# PinOut_5.net
KiCad netlist of a schematic drawn in EAGLE
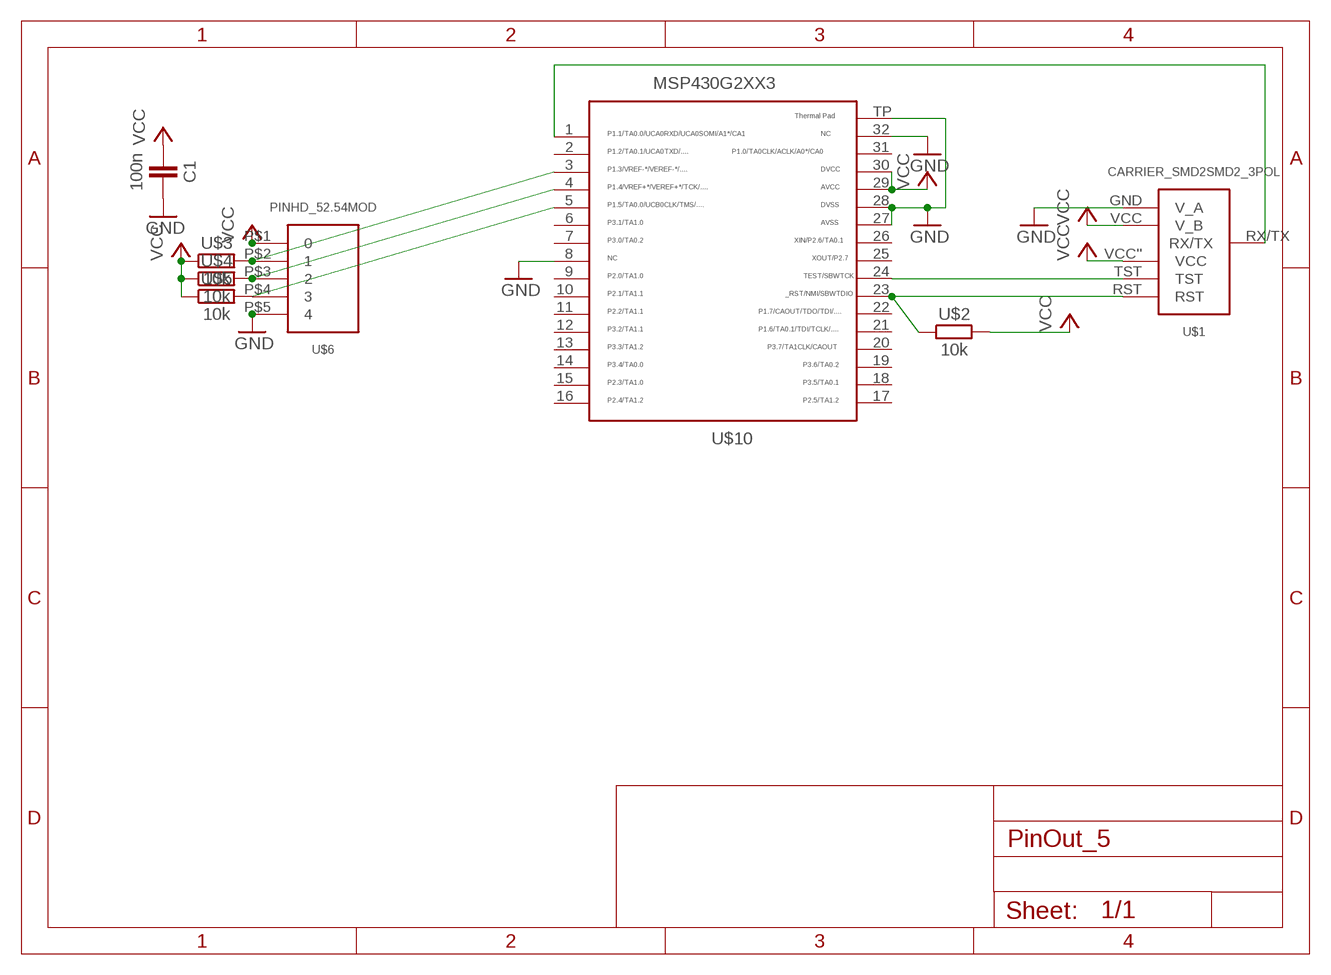
[diagram p0: schematic, sheet 1]

(export (version "E")
  (design (tool "Eeschema 10.0.6"))
  (components
    (comp (ref "C1")
      (value "100n")
      (footprint "eagle-import:603")
      (libsource (lib "eagle-import") (part "CAPACITOR"))
    )
    (comp (ref "U$1")
      (value "CARRIER_SMD2SMD2_3POL")
      (footprint "eagle-import:CARRIER_SMD2_3POL")
      (libsource (lib "eagle-import") (part "CARRIER_SMD2SMD2_3POL"))
    )
    (comp (ref "U$2")
      (value "10k")
      (footprint "eagle-import:603")
      (libsource (lib "eagle-import") (part "RESISTOR0603"))
    )
    (comp (ref "U$3")
      (value "10k")
      (footprint "eagle-import:1206")
      (libsource (lib "eagle-import") (part "RESISTOR1206"))
    )
    (comp (ref "U$4")
      (value "10k")
      (footprint "eagle-import:1206")
      (libsource (lib "eagle-import") (part "RESISTOR1206"))
    )
    (comp (ref "U$5")
      (value "10k")
      (footprint "eagle-import:1206")
      (libsource (lib "eagle-import") (part "RESISTOR1206"))
    )
    (comp (ref "U$6")
      (value "PINHD_52.54MOD")
      (footprint "eagle-import:PINHD_5_MOD")
      (libsource (lib "eagle-import") (part "PINHD_52.54MOD"))
    )
    (comp (ref "U$10")
      (value "MSP430G2553")
      (footprint "eagle-import:QFN32")
      (libsource (lib "eagle-import") (part "MSP430G2553"))
    )
  )
  (nets
    (net (code "1") (name "GND") (class "Default")
      (node (ref "C1") (pin "2") (pinfunction "2_2") (pintype "passive"))
      (node (ref "U$1") (pin "GND") (pinfunction "V_A_GND") (pintype "bidirectional"))
      (node (ref "U$10") (pin "27") (pinfunction "27_27") (pintype "bidirectional"))
      (node (ref "U$10") (pin "28") (pinfunction "28_28") (pintype "bidirectional"))
      (node (ref "U$10") (pin "32") (pinfunction "32_32") (pintype "bidirectional"))
      (node (ref "U$10") (pin "8") (pinfunction "8_8") (pintype "bidirectional"))
      (node (ref "U$10") (pin "TP") (pinfunction "TP_TP") (pintype "bidirectional"))
      (node (ref "U$6") (pin "P$5") (pinfunction "4_P$5") (pintype "bidirectional"))
    )
    (net (code "2") (name "Net-(U$1-PadRST)") (class "Default")
      (node (ref "U$1") (pin "RST") (pinfunction "RST_RST") (pintype "bidirectional"))
      (node (ref "U$10") (pin "23") (pinfunction "23_23") (pintype "bidirectional"))
      (node (ref "U$2") (pin "1") (pinfunction "1_1") (pintype "passive"))
    )
    (net (code "3") (name "Net-(U$1-PadRX{slash}TX)") (class "Default")
      (node (ref "U$1") (pin "RX/TX") (pinfunction "RX/TX_RX/TX") (pintype "bidirectional"))
      (node (ref "U$10") (pin "1") (pinfunction "1_1") (pintype "bidirectional"))
    )
    (net (code "4") (name "Net-(U$1-PadTST)") (class "Default")
      (node (ref "U$1") (pin "TST") (pinfunction "TST_TST") (pintype "bidirectional"))
      (node (ref "U$10") (pin "24") (pinfunction "24_24") (pintype "bidirectional"))
    )
    (net (code "5") (name "Net-(U$6-1)") (class "Default")
      (node (ref "U$10") (pin "3") (pinfunction "3_3") (pintype "bidirectional"))
      (node (ref "U$3") (pin "2") (pinfunction "2_2") (pintype "passive"))
      (node (ref "U$6") (pin "P$2") (pinfunction "1_P$2") (pintype "bidirectional"))
    )
    (net (code "6") (name "Net-(U$6-2)") (class "Default")
      (node (ref "U$10") (pin "4") (pinfunction "4_4") (pintype "bidirectional"))
      (node (ref "U$4") (pin "2") (pinfunction "2_2") (pintype "passive"))
      (node (ref "U$6") (pin "P$3") (pinfunction "2_P$3") (pintype "bidirectional"))
    )
    (net (code "7") (name "Net-(U$6-3)") (class "Default")
      (node (ref "U$10") (pin "5") (pinfunction "5_5") (pintype "bidirectional"))
      (node (ref "U$5") (pin "2") (pinfunction "2_2") (pintype "passive"))
      (node (ref "U$6") (pin "P$4") (pinfunction "3_P$4") (pintype "bidirectional"))
    )
    (net (code "8") (name "VCC") (class "Default")
      (node (ref "C1") (pin "1") (pinfunction "1_1") (pintype "passive"))
      (node (ref "U$1") (pin "VCC") (pinfunction "V_B_VCC") (pintype "bidirectional"))
      (node (ref "U$1") (pin "VCC''") (pinfunction "VCC_VCC''") (pintype "bidirectional"))
      (node (ref "U$10") (pin "29") (pinfunction "29_29") (pintype "bidirectional"))
      (node (ref "U$10") (pin "30") (pinfunction "30_30") (pintype "bidirectional"))
      (node (ref "U$2") (pin "2") (pinfunction "2_2") (pintype "passive"))
      (node (ref "U$3") (pin "1") (pinfunction "1_1") (pintype "passive"))
      (node (ref "U$4") (pin "1") (pinfunction "1_1") (pintype "passive"))
      (node (ref "U$5") (pin "1") (pinfunction "1_1") (pintype "passive"))
      (node (ref "U$6") (pin "P$1") (pinfunction "0_P$1") (pintype "bidirectional"))
    )
    (net (code "9") (name "unconnected-(U$10-Pad2)") (class "Default")
      (node (ref "U$10") (pin "2") (pinfunction "2_2") (pintype "bidirectional"))
    )
    (net (code "10") (name "unconnected-(U$10-Pad6)") (class "Default")
      (node (ref "U$10") (pin "6") (pinfunction "6_6") (pintype "bidirectional"))
    )
    (net (code "11") (name "unconnected-(U$10-Pad7)") (class "Default")
      (node (ref "U$10") (pin "7") (pinfunction "7_7") (pintype "bidirectional"))
    )
    (net (code "12") (name "unconnected-(U$10-Pad9)") (class "Default")
      (node (ref "U$10") (pin "9") (pinfunction "9_9") (pintype "bidirectional"))
    )
    (net (code "13") (name "unconnected-(U$10-Pad10)") (class "Default")
      (node (ref "U$10") (pin "10") (pinfunction "10_10") (pintype "bidirectional"))
    )
    (net (code "14") (name "unconnected-(U$10-Pad11)") (class "Default")
      (node (ref "U$10") (pin "11") (pinfunction "11_11") (pintype "bidirectional"))
    )
    (net (code "15") (name "unconnected-(U$10-Pad12)") (class "Default")
      (node (ref "U$10") (pin "12") (pinfunction "12_12") (pintype "bidirectional"))
    )
    (net (code "16") (name "unconnected-(U$10-Pad13)") (class "Default")
      (node (ref "U$10") (pin "13") (pinfunction "13_13") (pintype "bidirectional"))
    )
    (net (code "17") (name "unconnected-(U$10-Pad14)") (class "Default")
      (node (ref "U$10") (pin "14") (pinfunction "14_14") (pintype "bidirectional"))
    )
    (net (code "18") (name "unconnected-(U$10-Pad15)") (class "Default")
      (node (ref "U$10") (pin "15") (pinfunction "15_15") (pintype "bidirectional"))
    )
    (net (code "19") (name "unconnected-(U$10-Pad16)") (class "Default")
      (node (ref "U$10") (pin "16") (pinfunction "16_16") (pintype "bidirectional"))
    )
    (net (code "20") (name "unconnected-(U$10-Pad17)") (class "Default")
      (node (ref "U$10") (pin "17") (pinfunction "17_17") (pintype "bidirectional"))
    )
    (net (code "21") (name "unconnected-(U$10-Pad18)") (class "Default")
      (node (ref "U$10") (pin "18") (pinfunction "18_18") (pintype "bidirectional"))
    )
    (net (code "22") (name "unconnected-(U$10-Pad19)") (class "Default")
      (node (ref "U$10") (pin "19") (pinfunction "19_19") (pintype "bidirectional"))
    )
    (net (code "23") (name "unconnected-(U$10-Pad20)") (class "Default")
      (node (ref "U$10") (pin "20") (pinfunction "20_20") (pintype "bidirectional"))
    )
    (net (code "24") (name "unconnected-(U$10-Pad21)") (class "Default")
      (node (ref "U$10") (pin "21") (pinfunction "21_21") (pintype "bidirectional"))
    )
    (net (code "25") (name "unconnected-(U$10-Pad22)") (class "Default")
      (node (ref "U$10") (pin "22") (pinfunction "22_22") (pintype "bidirectional"))
    )
    (net (code "26") (name "unconnected-(U$10-Pad25)") (class "Default")
      (node (ref "U$10") (pin "25") (pinfunction "25_25") (pintype "bidirectional"))
    )
    (net (code "27") (name "unconnected-(U$10-Pad26)") (class "Default")
      (node (ref "U$10") (pin "26") (pinfunction "26_26") (pintype "bidirectional"))
    )
    (net (code "28") (name "unconnected-(U$10-Pad31)") (class "Default")
      (node (ref "U$10") (pin "31") (pinfunction "31_31") (pintype "bidirectional"))
    )
  )
)
